# Sheet.net
KiCad netlist of a schematic drawn in Altium Designer
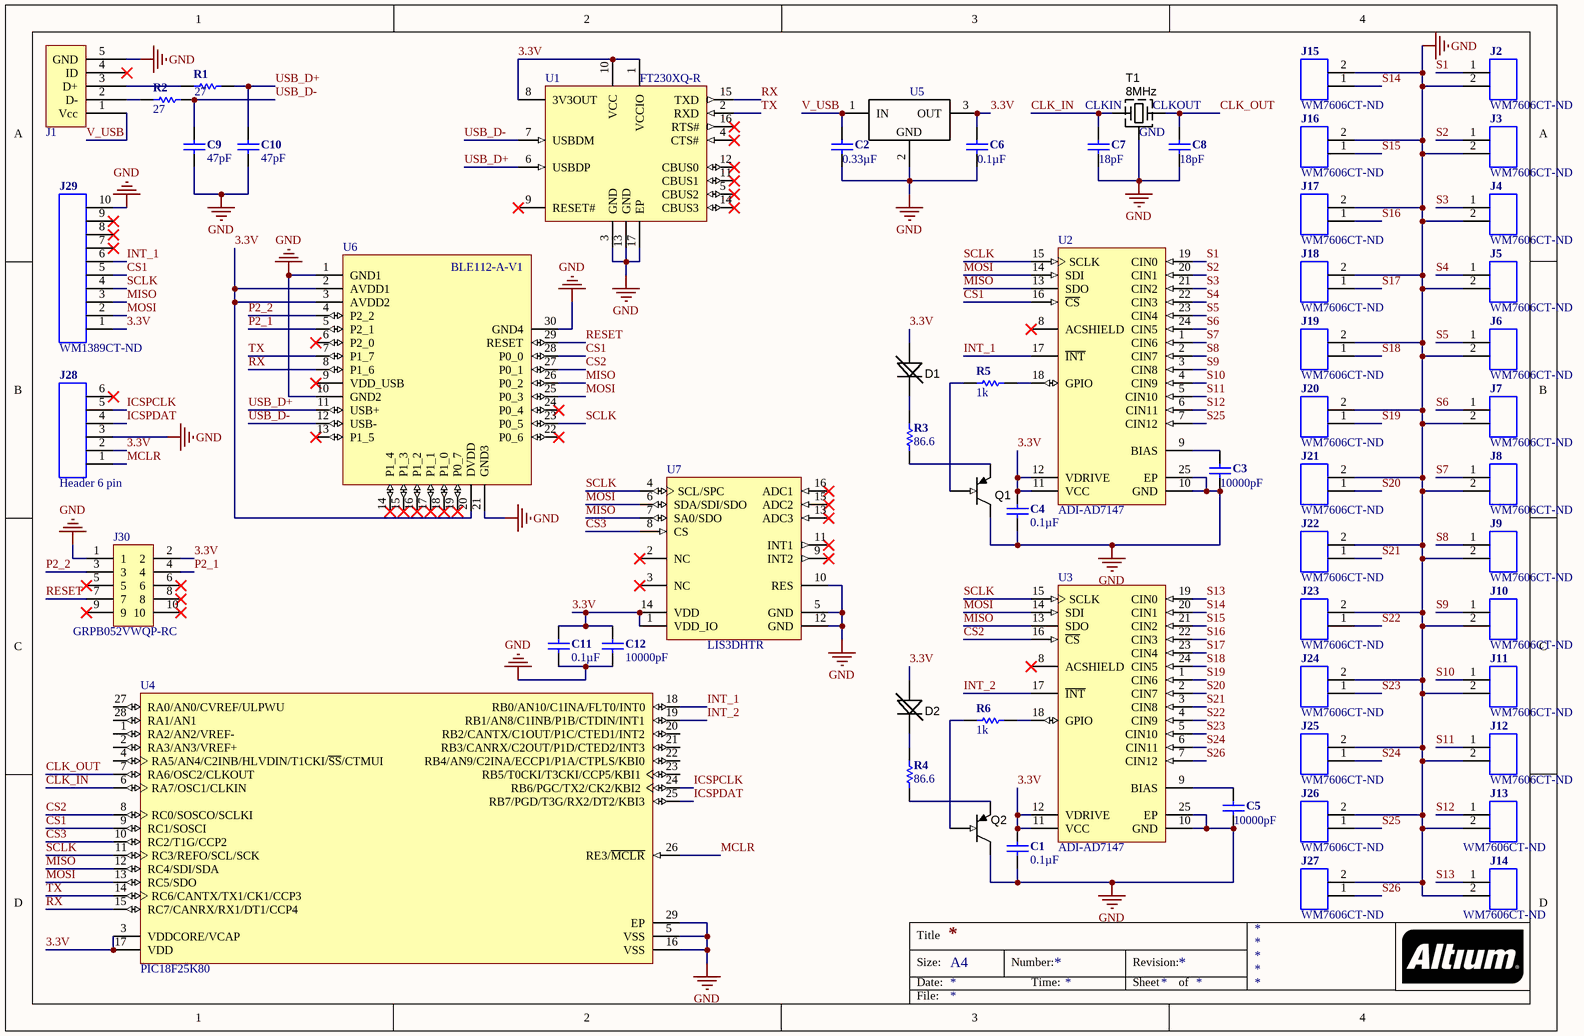
[diagram p0: Sheet.SchDoc]

(export (version "E")
  (design (tool "Eeschema 10.0.6"))
  (components
    (comp (ref "C1")
      (value "0.1µF")
      (footprint "CAP-0805(2012)-R")
      (description "___ OHM ___ mW 0805(2012) SMD")
      (fields
        (field (name "MANUFACTURER") "Yageo")
        (field (name "MANUFACTURER PART NUMBER") "CC0805KRX7R9BB104")
      )
      (libsource (lib "Glove") (part "C-0805(2012)"))
    )
    (comp (ref "C2")
      (value "0.33µF")
      (footprint "CAP-0805(2012)-R")
      (description "___ OHM ___ mW 0805(2012) SMD")
      (fields
        (field (name "MANUFACTURER") "Yageo")
        (field (name "MANUFACTURER PART NUMBER") "CC0805KKX7R7BB334")
      )
      (libsource (lib "Glove") (part "C-0805(2012)"))
    )
    (comp (ref "C3")
      (value "10000pF")
      (footprint "CAP-0805(2012)-R")
      (description "___ OHM ___ mW 0805(2012) SMD")
      (fields
        (field (name "MANUFACTURER") "Yageo")
        (field (name "MANUFACTURER PART NUMBER") "CC0805KRX7R9BB103")
      )
      (libsource (lib "Glove") (part "C-0805(2012)"))
    )
    (comp (ref "C4")
      (value "0.1µF")
      (footprint "CAP-0805(2012)-R")
      (description "___ OHM ___ mW 0805(2012) SMD")
      (fields
        (field (name "MANUFACTURER") "Yageo")
        (field (name "MANUFACTURER PART NUMBER") "CC0805KRX7R9BB104")
      )
      (libsource (lib "Glove") (part "C-0805(2012)"))
    )
    (comp (ref "C5")
      (value "10000pF")
      (footprint "CAP-0805(2012)-R")
      (description "___ OHM ___ mW 0805(2012) SMD")
      (fields
        (field (name "MANUFACTURER") "Yageo")
        (field (name "MANUFACTURER PART NUMBER") "CC0805KRX7R9BB103")
      )
      (libsource (lib "Glove") (part "C-0805(2012)"))
    )
    (comp (ref "C6")
      (value "0.1µF")
      (footprint "CAP-0805(2012)-R")
      (description "___ OHM ___ mW 0805(2012) SMD")
      (fields
        (field (name "MANUFACTURER") "Yageo")
        (field (name "MANUFACTURER PART NUMBER") "CC0805KRX7R9BB104")
      )
      (libsource (lib "Glove") (part "C-0805(2012)"))
    )
    (comp (ref "C7")
      (value "18pF")
      (footprint "CAP-0805(2012)-R")
      (description "___ OHM ___ mW 0805(2012) SMD")
      (fields
        (field (name "MANUFACTURER") "Yageo")
        (field (name "MANUFACTURER PART NUMBER") "CC0805JRNPO9BN180")
      )
      (libsource (lib "Glove") (part "C-0805(2012)"))
    )
    (comp (ref "C8")
      (value "18pF")
      (footprint "CAP-0805(2012)-R")
      (description "___ OHM ___ mW 0805(2012) SMD")
      (fields
        (field (name "MANUFACTURER") "Yageo")
        (field (name "MANUFACTURER PART NUMBER") "CC0805JRNPO9BN180")
      )
      (libsource (lib "Glove") (part "C-0805(2012)"))
    )
    (comp (ref "C9")
      (value "47pF")
      (footprint "CAP-0805(2012)-R")
      (description "___ OHM ___ mW 0805(2012) SMD")
      (fields
        (field (name "MANUFACTURER") "Yageo")
        (field (name "MANUFACTURER PART NUMBER") "CC0805JRNPO9BN470")
      )
      (libsource (lib "Glove") (part "C-0805(2012)"))
    )
    (comp (ref "C10")
      (value "47pF")
      (footprint "CAP-0805(2012)-R")
      (description "___ OHM ___ mW 0805(2012) SMD")
      (fields
        (field (name "MANUFACTURER") "Yageo")
        (field (name "MANUFACTURER PART NUMBER") "CC0805JRNPO9BN470")
      )
      (libsource (lib "Glove") (part "C-0805(2012)"))
    )
    (comp (ref "C11")
      (value "0.1µF")
      (footprint "CAP-0805(2012)-R")
      (description "___ OHM ___ mW 0805(2012) SMD")
      (fields
        (field (name "MANUFACTURER") "Yageo")
        (field (name "MANUFACTURER PART NUMBER") "CC0805KRX7R9BB104")
      )
      (libsource (lib "Glove") (part "C-0805(2012)"))
    )
    (comp (ref "C12")
      (value "10000pF")
      (footprint "CAP-0805(2012)-R")
      (description "___ OHM ___ mW 0805(2012) SMD")
      (fields
        (field (name "MANUFACTURER") "Yageo")
        (field (name "MANUFACTURER PART NUMBER") "CC0805KRX7R9BB103")
      )
      (libsource (lib "Glove") (part "C-0805(2012)"))
    )
    (comp (ref "D1")
      (value "YELLOW")
      (footprint "LED-0805-A")
      (description "LED, 0805 SMD, YELLOW")
      (fields
        (field (name "MANUFACTURER") "OSRAM Opto Semiconductors Inc.")
        (field (name "MANUFACTURER PART NUMBER") "LY R976-PS-36")
      )
      (libsource (lib "Glove") (part "LED_0805_YELLOW"))
    )
    (comp (ref "D2")
      (value "YELLOW")
      (footprint "LED-0805-A")
      (description "LED, 0805 SMD, YELLOW")
      (fields
        (field (name "MANUFACTURER") "OSRAM Opto Semiconductors Inc.")
        (field (name "MANUFACTURER PART NUMBER") "LY R976-PS-36")
      )
      (libsource (lib "Glove") (part "LED_0805_YELLOW"))
    )
    (comp (ref "J1")
      (value "USB")
      (footprint "USB_Connector_5P_MICRO_USB_FCI")
      (description "USB_Connector_5P_MICRO_USB_FCI")
      (fields (field (name "MANUFACTURER") "FCI") (field (name "MANUFACTURER PART NUMBER") "10118194-0001LF"))
      (libsource (lib "Glove") (part "USB"))
    )
    (comp (ref "J2")
      (value "Header 2 pin")
      (footprint "WM7606CT-ND")
      (description "Header, 2 pin, .1 pitch")
      (fields
        (field (name "MANUFACTURER") "Molex, LLC")
        (field (name "MANUFACTURER PART NUMBER") "0533980271")
        (field (name "SUPPLIER PART NUMBER 1") "WM7606CT-ND")
      )
      (libsource (lib "") (part "CON-2Pin_1"))
    )
    (comp (ref "J3")
      (value "Header 2 pin")
      (footprint "WM7606CT-ND")
      (description "Header, 2 pin, .1 pitch")
      (fields
        (field (name "MANUFACTURER") "Molex, LLC")
        (field (name "MANUFACTURER PART NUMBER") "0533980271")
        (field (name "SUPPLIER PART NUMBER 1") "WM7606CT-ND")
      )
      (libsource (lib "") (part "CON-2Pin_1"))
    )
    (comp (ref "J4")
      (value "Header 2 pin")
      (footprint "WM7606CT-ND")
      (description "Header, 2 pin, .1 pitch")
      (fields
        (field (name "MANUFACTURER") "Molex, LLC")
        (field (name "MANUFACTURER PART NUMBER") "0533980271")
        (field (name "SUPPLIER PART NUMBER 1") "WM7606CT-ND")
      )
      (libsource (lib "") (part "CON-2Pin_1"))
    )
    (comp (ref "J5")
      (value "Header 2 pin")
      (footprint "WM7606CT-ND")
      (description "Header, 2 pin, .1 pitch")
      (fields
        (field (name "MANUFACTURER") "Molex, LLC")
        (field (name "MANUFACTURER PART NUMBER") "0533980271")
        (field (name "SUPPLIER PART NUMBER 1") "WM7606CT-ND")
      )
      (libsource (lib "") (part "CON-2Pin_1"))
    )
    (comp (ref "J6")
      (value "Header 2 pin")
      (footprint "WM7606CT-ND")
      (description "Header, 2 pin, .1 pitch")
      (fields
        (field (name "MANUFACTURER") "Molex, LLC")
        (field (name "MANUFACTURER PART NUMBER") "0533980271")
        (field (name "SUPPLIER PART NUMBER 1") "WM7606CT-ND")
      )
      (libsource (lib "") (part "CON-2Pin_1"))
    )
    (comp (ref "J7")
      (value "Header 2 pin")
      (footprint "WM7606CT-ND")
      (description "Header, 2 pin, .1 pitch")
      (fields
        (field (name "MANUFACTURER") "Molex, LLC")
        (field (name "MANUFACTURER PART NUMBER") "0533980271")
        (field (name "SUPPLIER PART NUMBER 1") "WM7606CT-ND")
      )
      (libsource (lib "") (part "CON-2Pin_1"))
    )
    (comp (ref "J8")
      (value "Header 2 pin")
      (footprint "WM7606CT-ND")
      (description "Header, 2 pin, .1 pitch")
      (fields
        (field (name "MANUFACTURER") "Molex, LLC")
        (field (name "MANUFACTURER PART NUMBER") "0533980271")
        (field (name "SUPPLIER PART NUMBER 1") "WM7606CT-ND")
      )
      (libsource (lib "") (part "CON-2Pin_1"))
    )
    (comp (ref "J9")
      (value "Header 2 pin")
      (footprint "WM7606CT-ND")
      (description "Header, 2 pin, .1 pitch")
      (fields
        (field (name "MANUFACTURER") "Molex, LLC")
        (field (name "MANUFACTURER PART NUMBER") "0533980271")
        (field (name "SUPPLIER PART NUMBER 1") "WM7606CT-ND")
      )
      (libsource (lib "") (part "CON-2Pin_1"))
    )
    (comp (ref "J10")
      (value "Header 2 pin")
      (footprint "WM7606CT-ND")
      (description "Header, 2 pin, .1 pitch")
      (fields
        (field (name "MANUFACTURER") "Molex, LLC")
        (field (name "MANUFACTURER PART NUMBER") "0533980271")
        (field (name "SUPPLIER PART NUMBER 1") "WM7606CT-ND")
      )
      (libsource (lib "") (part "CON-2Pin_1"))
    )
    (comp (ref "J11")
      (value "Header 2 pin")
      (footprint "WM7606CT-ND")
      (description "Header, 2 pin, .1 pitch")
      (fields
        (field (name "MANUFACTURER") "Molex, LLC")
        (field (name "MANUFACTURER PART NUMBER") "0533980271")
        (field (name "SUPPLIER PART NUMBER 1") "WM7606CT-ND")
      )
      (libsource (lib "") (part "CON-2Pin_1"))
    )
    (comp (ref "J12")
      (value "Header 2 pin")
      (footprint "WM7606CT-ND")
      (description "Header, 2 pin, .1 pitch")
      (fields
        (field (name "MANUFACTURER") "Molex, LLC")
        (field (name "MANUFACTURER PART NUMBER") "0533980271")
        (field (name "SUPPLIER PART NUMBER 1") "WM7606CT-ND")
      )
      (libsource (lib "") (part "CON-2Pin_1"))
    )
    (comp (ref "J13")
      (value "Header 2 pin")
      (footprint "WM7606CT-ND")
      (description "Header, 2 pin, .1 pitch")
      (fields
        (field (name "MANUFACTURER") "Molex, LLC")
        (field (name "MANUFACTURER PART NUMBER") "0533980271")
        (field (name "SUPPLIER PART NUMBER 1") "WM7606CT-ND")
      )
      (libsource (lib "") (part "CON-2Pin_1"))
    )
    (comp (ref "J14")
      (value "Header 2 pin")
      (footprint "WM7606CT-ND")
      (description "Header, 2 pin, .1 pitch")
      (fields
        (field (name "MANUFACTURER") "Molex, LLC")
        (field (name "MANUFACTURER PART NUMBER") "0533980271")
        (field (name "SUPPLIER PART NUMBER 1") "WM7606CT-ND")
      )
      (libsource (lib "") (part "CON-2Pin_1"))
    )
    (comp (ref "J15")
      (value "Header 2 pin")
      (footprint "WM7606CT-ND")
      (description "Header, 2 pin, .1 pitch")
      (fields
        (field (name "MANUFACTURER") "Molex, LLC")
        (field (name "MANUFACTURER PART NUMBER") "0533980271")
        (field (name "SUPPLIER PART NUMBER 1") "WM7606CT-ND")
      )
      (libsource (lib "Glove") (part "CON-2Pin"))
    )
    (comp (ref "J16")
      (value "Header 2 pin")
      (footprint "WM7606CT-ND")
      (description "Header, 2 pin, .1 pitch")
      (fields
        (field (name "MANUFACTURER") "Molex, LLC")
        (field (name "MANUFACTURER PART NUMBER") "0533980271")
        (field (name "SUPPLIER PART NUMBER 1") "WM7606CT-ND")
      )
      (libsource (lib "Glove") (part "CON-2Pin"))
    )
    (comp (ref "J17")
      (value "Header 2 pin")
      (footprint "WM7606CT-ND")
      (description "Header, 2 pin, .1 pitch")
      (fields
        (field (name "MANUFACTURER") "Molex, LLC")
        (field (name "MANUFACTURER PART NUMBER") "0533980271")
        (field (name "SUPPLIER PART NUMBER 1") "WM7606CT-ND")
      )
      (libsource (lib "Glove") (part "CON-2Pin"))
    )
    (comp (ref "J18")
      (value "Header 2 pin")
      (footprint "WM7606CT-ND")
      (description "Header, 2 pin, .1 pitch")
      (fields
        (field (name "MANUFACTURER") "Molex, LLC")
        (field (name "MANUFACTURER PART NUMBER") "0533980271")
        (field (name "SUPPLIER PART NUMBER 1") "WM7606CT-ND")
      )
      (libsource (lib "Glove") (part "CON-2Pin"))
    )
    (comp (ref "J19")
      (value "Header 2 pin")
      (footprint "WM7606CT-ND")
      (description "Header, 2 pin, .1 pitch")
      (fields
        (field (name "MANUFACTURER") "Molex, LLC")
        (field (name "MANUFACTURER PART NUMBER") "0533980271")
        (field (name "SUPPLIER PART NUMBER 1") "WM7606CT-ND")
      )
      (libsource (lib "Glove") (part "CON-2Pin"))
    )
    (comp (ref "J20")
      (value "Header 2 pin")
      (footprint "WM7606CT-ND")
      (description "Header, 2 pin, .1 pitch")
      (fields
        (field (name "MANUFACTURER") "Molex, LLC")
        (field (name "MANUFACTURER PART NUMBER") "0533980271")
        (field (name "SUPPLIER PART NUMBER 1") "WM7606CT-ND")
      )
      (libsource (lib "Glove") (part "CON-2Pin"))
    )
    (comp (ref "J21")
      (value "Header 2 pin")
      (footprint "WM7606CT-ND")
      (description "Header, 2 pin, .1 pitch")
      (fields
        (field (name "MANUFACTURER") "Molex, LLC")
        (field (name "MANUFACTURER PART NUMBER") "0533980271")
        (field (name "SUPPLIER PART NUMBER 1") "WM7606CT-ND")
      )
      (libsource (lib "Glove") (part "CON-2Pin"))
    )
    (comp (ref "J22")
      (value "Header 2 pin")
      (footprint "WM7606CT-ND")
      (description "Header, 2 pin, .1 pitch")
      (fields
        (field (name "MANUFACTURER") "Molex, LLC")
        (field (name "MANUFACTURER PART NUMBER") "0533980271")
        (field (name "SUPPLIER PART NUMBER 1") "WM7606CT-ND")
      )
      (libsource (lib "Glove") (part "CON-2Pin"))
    )
    (comp (ref "J23")
      (value "Header 2 pin")
      (footprint "WM7606CT-ND")
      (description "Header, 2 pin, .1 pitch")
      (fields
        (field (name "MANUFACTURER") "Molex, LLC")
        (field (name "MANUFACTURER PART NUMBER") "0533980271")
        (field (name "SUPPLIER PART NUMBER 1") "WM7606CT-ND")
      )
      (libsource (lib "Glove") (part "CON-2Pin"))
    )
    (comp (ref "J24")
      (value "Header 2 pin")
      (footprint "WM7606CT-ND")
      (description "Header, 2 pin, .1 pitch")
      (fields
        (field (name "MANUFACTURER") "Molex, LLC")
        (field (name "MANUFACTURER PART NUMBER") "0533980271")
        (field (name "SUPPLIER PART NUMBER 1") "WM7606CT-ND")
      )
      (libsource (lib "Glove") (part "CON-2Pin"))
    )
    (comp (ref "J25")
      (value "Header 2 pin")
      (footprint "WM7606CT-ND")
      (description "Header, 2 pin, .1 pitch")
      (fields
        (field (name "MANUFACTURER") "Molex, LLC")
        (field (name "MANUFACTURER PART NUMBER") "0533980271")
        (field (name "SUPPLIER PART NUMBER 1") "WM7606CT-ND")
      )
      (libsource (lib "Glove") (part "CON-2Pin"))
    )
    (comp (ref "J26")
      (value "Header 2 pin")
      (footprint "WM7606CT-ND")
      (description "Header, 2 pin, .1 pitch")
      (fields
        (field (name "MANUFACTURER") "Molex, LLC")
        (field (name "MANUFACTURER PART NUMBER") "0533980271")
        (field (name "SUPPLIER PART NUMBER 1") "WM7606CT-ND")
      )
      (libsource (lib "Glove") (part "CON-2Pin"))
    )
    (comp (ref "J27")
      (value "Header 2 pin")
      (footprint "WM7606CT-ND")
      (description "Header, 2 pin, .1 pitch")
      (fields
        (field (name "MANUFACTURER") "Molex, LLC")
        (field (name "MANUFACTURER PART NUMBER") "0533980271")
        (field (name "SUPPLIER PART NUMBER 1") "WM7606CT-ND")
      )
      (libsource (lib "Glove") (part "CON-2Pin"))
    )
    (comp (ref "J28")
      (value "Header 6 pin")
      (footprint "HEADER-6-100mil")
      (description "Header, 6 pin, .1 pitch")
      (fields
        (field (name "MANUFACTURER") "TE Connectivity / AMP")
        (field (name "MANUFACTURER PART NUMBER") "4-103327-6")
      )
      (libsource (lib "Glove") (part "CON-6Pin-100Mil"))
    )
    (comp (ref "J29")
      (value "Header 10 pin")
      (footprint "MOLEX-503480-1000")
      (description "Header, 10 pin, .50mm pitch")
      (fields
        (field (name "MANUFACTURER") "Molex, LLC")
        (field (name "MANUFACTURER PART NUMBER") "5034801000")
        (field (name "SUPPLIER PART NUMBER 1") "WM1389CT-ND")
      )
      (libsource (lib "Glove") (part "WM1389CT-ND"))
    )
    (comp (ref "J30")
      (value "GRPB052VWQP-RC")
      (footprint "GRPB052VWQP-RC")
      (description "CONN HEADER .050\" 10PS DL SMD AU")
      (fields (field (name "MANUFACTURER") "Sullins Connector Solutions"))
      (libsource (lib "UCSD Protolab") (part "GRPB052VWQP-RC"))
    )
    (comp (ref "Q1")
      (value "~")
      (footprint "SOT23-3")
      (description "Transistor PNP")
      (fields
        (field (name "MANUFACTURER") "Diodes Incorporated")
        (field (name "MANUFACTURER PART NUMBER") "FMMT591TA")
      )
      (libsource (lib "Glove") (part "FMMT591CT-ND"))
    )
    (comp (ref "Q2")
      (value "~")
      (footprint "SOT23-3")
      (description "Transistor PNP")
      (fields
        (field (name "MANUFACTURER") "Diodes Incorporated")
        (field (name "MANUFACTURER PART NUMBER") "FMMT591TA")
      )
      (libsource (lib "Glove") (part "FMMT591CT-ND"))
    )
    (comp (ref "R1")
      (value "27")
      (footprint "R-0805(2012)-R")
      (description "___ OHM ___ mW 0805(2012) SMD")
      (fields
        (field (name "MANUFACTURER") "Yageo")
        (field (name "MANUFACTURER PART NUMBER") "RC0805FR-0727RL")
      )
      (libsource (lib "Glove") (part "R-0805(2012)"))
    )
    (comp (ref "R2")
      (value "27")
      (footprint "R-0805(2012)-R")
      (description "___ OHM ___ mW 0805(2012) SMD")
      (fields
        (field (name "MANUFACTURER") "Yageo")
        (field (name "MANUFACTURER PART NUMBER") "RC0805FR-0727RL")
      )
      (libsource (lib "Glove") (part "R-0805(2012)"))
    )
    (comp (ref "R3")
      (value "86.6")
      (footprint "R-0805(2012)-R")
      (description "___ OHM ___ mW 0805(2012) SMD")
      (fields
        (field (name "MANUFACTURER") "Yageo")
        (field (name "MANUFACTURER PART NUMBER") "RC0805FR-0786R6L")
      )
      (libsource (lib "CLB-Schematic-Library") (part "R-0805(2012)"))
    )
    (comp (ref "R4")
      (value "86.6")
      (footprint "R-0805(2012)-R")
      (description "___ OHM ___ mW 0805(2012) SMD")
      (fields
        (field (name "MANUFACTURER") "Yageo")
        (field (name "MANUFACTURER PART NUMBER") "RC0805FR-0786R6L")
      )
      (libsource (lib "CLB-Schematic-Library") (part "R-0805(2012)"))
    )
    (comp (ref "R5")
      (value "1k")
      (footprint "R-0805(2012)-R")
      (description "___ OHM ___ mW 0805(2012) SMD")
      (fields
        (field (name "MANUFACTURER") "Yageo")
        (field (name "MANUFACTURER PART NUMBER") "RC0805JR-071KL")
      )
      (libsource (lib "Glove") (part "R-0805(2012)"))
    )
    (comp (ref "R6")
      (value "1k")
      (footprint "R-0805(2012)-R")
      (description "___ OHM ___ mW 0805(2012) SMD")
      (fields
        (field (name "MANUFACTURER") "Yageo")
        (field (name "MANUFACTURER PART NUMBER") "RC0805JR-071KL")
      )
      (libsource (lib "Glove") (part "R-0805(2012)"))
    )
    (comp (ref "T1")
      (value "8MHz")
      (footprint "CRYSTAL-8MHZ")
      (description "Oscillator Crystal 8MHz 10ppm")
      (fields
        (field (name "MANUFACTURER") "ABRACON")
        (field (name "MANUFACTURER PART NUMBER") "ABMM2-8.000MHZ-E2-T")
      )
      (libsource (lib "Glove") (part "CRYSTAL_8MHz"))
    )
    (comp (ref "U1")
      (value "FT230XQ-R")
      (footprint "QFN-16")
      (fields (field (name "MANUFACTURER") "FTDI"))
      (libsource (lib "Glove") (part "FT230XQ-R"))
    )
    (comp (ref "U2")
      (value "ADI-AD7147")
      (footprint "LFCSP_WQ")
      (libsource (lib "Glove") (part "ADI-AD7147"))
    )
    (comp (ref "U3")
      (value "ADI-AD7147")
      (footprint "LFCSP_WQ")
      (libsource (lib "Glove") (part "ADI-AD7147"))
    )
    (comp (ref "U4")
      (value "PIC18F25K80")
      (footprint "MCHP-QFN-S-MM28_N")
      (libsource (lib "Glove") (part "PIC18F25K80"))
    )
    (comp (ref "U5")
      (value "L78L33ACUTR")
      (footprint "SOT89-3")
      (fields (field (name "MANUFACTURER") "STMicroelectronics"))
      (libsource (lib "Glove") (part "L78L33ACUTR"))
    )
    (comp (ref "U6")
      (value "BLE112-A-V1")
      (footprint "BLE112-A-V1")
      (description "CLASS 2 BLTOOTH 4.0 MODULE")
      (fields (field (name "MANUFACTURER") "Silicon Labs"))
      (libsource (lib "UCSD Protolab") (part "BLE112-A-V1"))
    )
    (comp (ref "U7")
      (value "LIS3DHTR")
      (footprint "STM-LGA-16_N")
      (fields (field (name "MANUFACTURER") "STMicroelectronics"))
      (libsource (lib "Altium Content Vault") (part "STM-LIS3DH-LGA-16"))
    )
  )
  (nets
    (net (code "1") (name "/3.3V") (class "Default")
      (node (ref "C1") (pin "1") (pinfunction "1_1") (pintype "passive"))
      (node (ref "C11") (pin "2") (pinfunction "2_2") (pintype "passive"))
      (node (ref "C12") (pin "2") (pinfunction "2_2") (pintype "passive"))
      (node (ref "C4") (pin "1") (pinfunction "1_1") (pintype "passive"))
      (node (ref "C6") (pin "1") (pinfunction "1_1") (pintype "passive"))
      (node (ref "D1") (pin "A") (pinfunction "A_A") (pintype "passive"))
      (node (ref "D2") (pin "A") (pinfunction "A_A") (pintype "passive"))
      (node (ref "J28") (pin "2") (pinfunction "2_2") (pintype "passive"))
      (node (ref "J29") (pin "1") (pinfunction "1_1") (pintype "passive"))
      (node (ref "J30") (pin "2") (pinfunction "2_2") (pintype "passive"))
      (node (ref "U1") (pin "1") (pinfunction "VCCIO_1") (pintype "power_in"))
      (node (ref "U1") (pin "10") (pinfunction "VCC_10") (pintype "power_in"))
      (node (ref "U1") (pin "8") (pinfunction "3V3OUT_8") (pintype "power_in"))
      (node (ref "U2") (pin "11") (pinfunction "VCC_11") (pintype "power_in"))
      (node (ref "U2") (pin "12") (pinfunction "VDRIVE_12") (pintype "power_in"))
      (node (ref "U3") (pin "11") (pinfunction "VCC_11") (pintype "power_in"))
      (node (ref "U3") (pin "12") (pinfunction "VDRIVE_12") (pintype "power_in"))
      (node (ref "U4") (pin "17") (pinfunction "VDD_17") (pintype "power_in"))
      (node (ref "U4") (pin "3") (pinfunction "VDDCORE/VCAP_3") (pintype "power_in"))
      (node (ref "U5") (pin "3") (pinfunction "OUT_3") (pintype "power_in"))
      (node (ref "U6") (pin "2") (pinfunction "AVDD1_2") (pintype "power_in"))
      (node (ref "U6") (pin "20") (pinfunction "DVDD_20") (pintype "power_in"))
      (node (ref "U6") (pin "3") (pinfunction "AVDD2_3") (pintype "power_in"))
      (node (ref "U7") (pin "1") (pinfunction "VDD_IO_1") (pintype "power_in"))
      (node (ref "U7") (pin "14") (pinfunction "VDD_14") (pintype "power_in"))
    )
    (net (code "2") (name "/CLK_IN") (class "Default")
      (node (ref "C7") (pin "1") (pinfunction "1_1") (pintype "passive"))
      (node (ref "T1") (pin "1") (pinfunction "CLKIN_1") (pintype "passive"))
      (node (ref "U4") (pin "6") (pinfunction "RA7/OSC1/CLKIN_6") (pintype "bidirectional"))
    )
    (net (code "3") (name "/CLK_OUT") (class "Default")
      (node (ref "C8") (pin "1") (pinfunction "1_1") (pintype "passive"))
      (node (ref "T1") (pin "3") (pinfunction "X_3") (pintype "passive"))
      (node (ref "U4") (pin "7") (pinfunction "RA6/OSC2/CLKOUT_7") (pintype "bidirectional"))
    )
    (net (code "4") (name "/CS1") (class "Default")
      (node (ref "J29") (pin "5") (pinfunction "5_5") (pintype "passive"))
      (node (ref "U2") (pin "16") (pinfunction "~{CS}_16") (pintype "input"))
      (node (ref "U4") (pin "9") (pinfunction "RC1/SOSCI_9") (pintype "bidirectional"))
      (node (ref "U6") (pin "28") (pinfunction "P0_0_28") (pintype "bidirectional"))
    )
    (net (code "5") (name "/CS2") (class "Default")
      (node (ref "U3") (pin "16") (pinfunction "~{CS}_16") (pintype "input"))
      (node (ref "U4") (pin "8") (pinfunction "RC0/SOSCO/SCLKI_8") (pintype "bidirectional"))
      (node (ref "U6") (pin "27") (pinfunction "P0_1_27") (pintype "bidirectional"))
    )
    (net (code "6") (name "/CS3") (class "Default")
      (node (ref "U4") (pin "10") (pinfunction "RC2/T1G/CCP2_10") (pintype "bidirectional"))
      (node (ref "U7") (pin "8") (pinfunction "CS_8") (pintype "input"))
    )
    (net (code "7") (name "/ICSPCLK") (class "Default")
      (node (ref "J28") (pin "5") (pinfunction "5_5") (pintype "passive"))
      (node (ref "U4") (pin "24") (pinfunction "RB6/PGC/TX2/CK2/KBI2_24") (pintype "bidirectional"))
    )
    (net (code "8") (name "/ICSPDAT") (class "Default")
      (node (ref "J28") (pin "4") (pinfunction "4_4") (pintype "passive"))
      (node (ref "U4") (pin "25") (pinfunction "RB7/PGD/T3G/RX2/DT2/KBI3_25") (pintype "bidirectional"))
    )
    (net (code "9") (name "/INT_1") (class "Default")
      (node (ref "J29") (pin "6") (pinfunction "6_6") (pintype "passive"))
      (node (ref "U2") (pin "17") (pinfunction "~{INT}_17") (pintype "open_collector"))
      (node (ref "U4") (pin "18") (pinfunction "RB0/AN10/C1INA/FLT0/INT0_18") (pintype "bidirectional"))
    )
    (net (code "10") (name "/INT_2") (class "Default")
      (node (ref "U3") (pin "17") (pinfunction "~{INT}_17") (pintype "open_collector"))
      (node (ref "U4") (pin "19") (pinfunction "RB1/AN8/C1INB/P1B/CTDIN/INT1_19") (pintype "bidirectional"))
    )
    (net (code "11") (name "/MCLR") (class "Default")
      (node (ref "J28") (pin "1") (pinfunction "1_1") (pintype "passive"))
      (node (ref "U4") (pin "26") (pinfunction "RE3/~{MCLR}_26") (pintype "input"))
    )
    (net (code "12") (name "/MISO") (class "Default")
      (node (ref "J29") (pin "3") (pinfunction "3_3") (pintype "passive"))
      (node (ref "U2") (pin "13") (pinfunction "SDO_13") (pintype "tri_state"))
      (node (ref "U3") (pin "13") (pinfunction "SDO_13") (pintype "tri_state"))
      (node (ref "U4") (pin "12") (pinfunction "RC4/SDI/SDA_12") (pintype "bidirectional"))
      (node (ref "U6") (pin "26") (pinfunction "P0_2_26") (pintype "bidirectional"))
      (node (ref "U7") (pin "7") (pinfunction "SA0/SDO_7") (pintype "bidirectional"))
    )
    (net (code "13") (name "/MOSI") (class "Default")
      (node (ref "J29") (pin "2") (pinfunction "2_2") (pintype "passive"))
      (node (ref "U2") (pin "14") (pinfunction "SDI_14") (pintype "input"))
      (node (ref "U3") (pin "14") (pinfunction "SDI_14") (pintype "input"))
      (node (ref "U4") (pin "13") (pinfunction "RC5/SDO_13") (pintype "bidirectional"))
      (node (ref "U6") (pin "25") (pinfunction "P0_3_25") (pintype "bidirectional"))
      (node (ref "U7") (pin "6") (pinfunction "SDA/SDI/SDO_6") (pintype "bidirectional"))
    )
    (net (code "14") (name "/P2_1") (class "Default")
      (node (ref "J30") (pin "4") (pinfunction "4_4") (pintype "passive"))
      (node (ref "U6") (pin "5") (pinfunction "P2_1_5") (pintype "bidirectional"))
    )
    (net (code "15") (name "/P2_2") (class "Default")
      (node (ref "J30") (pin "3") (pinfunction "3_3") (pintype "passive"))
      (node (ref "U6") (pin "4") (pinfunction "P2_2_4") (pintype "bidirectional"))
    )
    (net (code "16") (name "/RESET") (class "Default")
      (node (ref "J30") (pin "7") (pinfunction "7_7") (pintype "passive"))
      (node (ref "U6") (pin "29") (pinfunction "RESET_29") (pintype "bidirectional"))
    )
    (net (code "17") (name "/RX") (class "Default")
      (node (ref "U1") (pin "15") (pinfunction "TXD_15") (pintype "output"))
      (node (ref "U4") (pin "15") (pinfunction "RC7/CANRX/RX1/DT1/CCP4_15") (pintype "bidirectional"))
      (node (ref "U6") (pin "8") (pinfunction "P1_6_8") (pintype "bidirectional"))
    )
    (net (code "18") (name "/S1") (class "Default")
      (node (ref "J2") (pin "1") (pinfunction "1_1") (pintype "passive"))
      (node (ref "U2") (pin "19") (pinfunction "CIN0_19") (pintype "input"))
    )
    (net (code "19") (name "/S2") (class "Default")
      (node (ref "J3") (pin "1") (pinfunction "1_1") (pintype "passive"))
      (node (ref "U2") (pin "20") (pinfunction "CIN1_20") (pintype "input"))
    )
    (net (code "20") (name "/S3") (class "Default")
      (node (ref "J4") (pin "1") (pinfunction "1_1") (pintype "passive"))
      (node (ref "U2") (pin "21") (pinfunction "CIN2_21") (pintype "input"))
    )
    (net (code "21") (name "/S4") (class "Default")
      (node (ref "J5") (pin "1") (pinfunction "1_1") (pintype "passive"))
      (node (ref "U2") (pin "22") (pinfunction "CIN3_22") (pintype "input"))
    )
    (net (code "22") (name "/S5") (class "Default")
      (node (ref "J6") (pin "1") (pinfunction "1_1") (pintype "passive"))
      (node (ref "U2") (pin "23") (pinfunction "CIN4_23") (pintype "input"))
    )
    (net (code "23") (name "/S6") (class "Default")
      (node (ref "J7") (pin "1") (pinfunction "1_1") (pintype "passive"))
      (node (ref "U2") (pin "24") (pinfunction "CIN5_24") (pintype "input"))
    )
    (net (code "24") (name "/S7") (class "Default")
      (node (ref "J8") (pin "1") (pinfunction "1_1") (pintype "passive"))
      (node (ref "U2") (pin "1") (pinfunction "CIN6_1") (pintype "input"))
    )
    (net (code "25") (name "/S8") (class "Default")
      (node (ref "J9") (pin "1") (pinfunction "1_1") (pintype "passive"))
      (node (ref "U2") (pin "2") (pinfunction "CIN7_2") (pintype "input"))
    )
    (net (code "26") (name "/S9") (class "Default")
      (node (ref "J10") (pin "1") (pinfunction "1_1") (pintype "passive"))
      (node (ref "U2") (pin "3") (pinfunction "CIN8_3") (pintype "input"))
    )
    (net (code "27") (name "/S10") (class "Default")
      (node (ref "J11") (pin "1") (pinfunction "1_1") (pintype "passive"))
      (node (ref "U2") (pin "4") (pinfunction "CIN9_4") (pintype "input"))
    )
    (net (code "28") (name "/S11") (class "Default")
      (node (ref "J12") (pin "1") (pinfunction "1_1") (pintype "passive"))
      (node (ref "U2") (pin "5") (pinfunction "CIN10_5") (pintype "input"))
    )
    (net (code "29") (name "/S12") (class "Default")
      (node (ref "J13") (pin "1") (pinfunction "1_1") (pintype "passive"))
      (node (ref "U2") (pin "6") (pinfunction "CIN11_6") (pintype "input"))
    )
    (net (code "30") (name "/S13") (class "Default")
      (node (ref "J14") (pin "1") (pinfunction "1_1") (pintype "passive"))
      (node (ref "U3") (pin "19") (pinfunction "CIN0_19") (pintype "input"))
    )
    (net (code "31") (name "/S14") (class "Default")
      (node (ref "J15") (pin "1") (pinfunction "1_1") (pintype "passive"))
      (node (ref "U3") (pin "20") (pinfunction "CIN1_20") (pintype "input"))
    )
    (net (code "32") (name "/S15") (class "Default")
      (node (ref "J16") (pin "1") (pinfunction "1_1") (pintype "passive"))
      (node (ref "U3") (pin "21") (pinfunction "CIN2_21") (pintype "input"))
    )
    (net (code "33") (name "/S16") (class "Default")
      (node (ref "J17") (pin "1") (pinfunction "1_1") (pintype "passive"))
      (node (ref "U3") (pin "22") (pinfunction "CIN3_22") (pintype "input"))
    )
    (net (code "34") (name "/S17") (class "Default")
      (node (ref "J18") (pin "1") (pinfunction "1_1") (pintype "passive"))
      (node (ref "U3") (pin "23") (pinfunction "CIN4_23") (pintype "input"))
    )
    (net (code "35") (name "/S18") (class "Default")
      (node (ref "J19") (pin "1") (pinfunction "1_1") (pintype "passive"))
      (node (ref "U3") (pin "24") (pinfunction "CIN5_24") (pintype "input"))
    )
    (net (code "36") (name "/S19") (class "Default")
      (node (ref "J20") (pin "1") (pinfunction "1_1") (pintype "passive"))
      (node (ref "U3") (pin "1") (pinfunction "CIN6_1") (pintype "input"))
    )
    (net (code "37") (name "/S20") (class "Default")
      (node (ref "J21") (pin "1") (pinfunction "1_1") (pintype "passive"))
      (node (ref "U3") (pin "2") (pinfunction "CIN7_2") (pintype "input"))
    )
    (net (code "38") (name "/S21") (class "Default")
      (node (ref "J22") (pin "1") (pinfunction "1_1") (pintype "passive"))
      (node (ref "U3") (pin "3") (pinfunction "CIN8_3") (pintype "input"))
    )
    (net (code "39") (name "/S22") (class "Default")
      (node (ref "J23") (pin "1") (pinfunction "1_1") (pintype "passive"))
      (node (ref "U3") (pin "4") (pinfunction "CIN9_4") (pintype "input"))
    )
    (net (code "40") (name "/S23") (class "Default")
      (node (ref "J24") (pin "1") (pinfunction "1_1") (pintype "passive"))
      (node (ref "U3") (pin "5") (pinfunction "CIN10_5") (pintype "input"))
    )
    (net (code "41") (name "/S24") (class "Default")
      (node (ref "J25") (pin "1") (pinfunction "1_1") (pintype "passive"))
      (node (ref "U3") (pin "6") (pinfunction "CIN11_6") (pintype "input"))
    )
    (net (code "42") (name "/S25") (class "Default")
      (node (ref "J26") (pin "1") (pinfunction "1_1") (pintype "passive"))
      (node (ref "U2") (pin "7") (pinfunction "CIN12_7") (pintype "input"))
    )
    (net (code "43") (name "/S26") (class "Default")
      (node (ref "J27") (pin "1") (pinfunction "1_1") (pintype "passive"))
      (node (ref "U3") (pin "7") (pinfunction "CIN12_7") (pintype "input"))
    )
    (net (code "44") (name "/SCLK") (class "Default")
      (node (ref "J29") (pin "4") (pinfunction "4_4") (pintype "passive"))
      (node (ref "U2") (pin "15") (pinfunction "SCLK_15") (pintype "input"))
      (node (ref "U3") (pin "15") (pinfunction "SCLK_15") (pintype "input"))
      (node (ref "U4") (pin "11") (pinfunction "RC3/REFO/SCL/SCK_11") (pintype "bidirectional"))
      (node (ref "U6") (pin "23") (pinfunction "P0_5_23") (pintype "bidirectional"))
      (node (ref "U7") (pin "4") (pinfunction "SCL/SPC_4") (pintype "bidirectional"))
    )
    (net (code "45") (name "/TX") (class "Default")
      (node (ref "U1") (pin "2") (pinfunction "RXD_2") (pintype "input"))
      (node (ref "U4") (pin "14") (pinfunction "RC6/CANTX/TX1/CK1/CCP3_14") (pintype "bidirectional"))
      (node (ref "U6") (pin "7") (pinfunction "P1_7_7") (pintype "bidirectional"))
    )
    (net (code "46") (name "/USB_D+") (class "Default")
      (node (ref "C10") (pin "2") (pinfunction "2_2") (pintype "passive"))
      (node (ref "R1") (pin "2") (pinfunction "2_2") (pintype "passive"))
      (node (ref "U1") (pin "6") (pinfunction "USBDP_6") (pintype "input"))
      (node (ref "U6") (pin "11") (pinfunction "USB+_11") (pintype "bidirectional"))
    )
    (net (code "47") (name "/USB_D-") (class "Default")
      (node (ref "C9") (pin "2") (pinfunction "2_2") (pintype "passive"))
      (node (ref "R2") (pin "2") (pinfunction "2_2") (pintype "passive"))
      (node (ref "U1") (pin "7") (pinfunction "USBDM_7") (pintype "input"))
      (node (ref "U6") (pin "12") (pinfunction "USB-_12") (pintype "bidirectional"))
    )
    (net (code "48") (name "/V_USB") (class "Default")
      (node (ref "C2") (pin "1") (pinfunction "1_1") (pintype "passive"))
      (node (ref "J1") (pin "1") (pinfunction "Vcc_1") (pintype "passive"))
      (node (ref "U5") (pin "1") (pinfunction "IN_1") (pintype "passive"))
    )
    (net (code "49") (name "GND") (class "Default")
      (node (ref "C1") (pin "2") (pinfunction "2_2") (pintype "passive"))
      (node (ref "C10") (pin "1") (pinfunction "1_1") (pintype "passive"))
      (node (ref "C11") (pin "1") (pinfunction "1_1") (pintype "passive"))
      (node (ref "C12") (pin "1") (pinfunction "1_1") (pintype "passive"))
      (node (ref "C2") (pin "2") (pinfunction "2_2") (pintype "passive"))
      (node (ref "C3") (pin "2") (pinfunction "2_2") (pintype "passive"))
      (node (ref "C4") (pin "2") (pinfunction "2_2") (pintype "passive"))
      (node (ref "C5") (pin "2") (pinfunction "2_2") (pintype "passive"))
      (node (ref "C6") (pin "2") (pinfunction "2_2") (pintype "passive"))
      (node (ref "C7") (pin "2") (pinfunction "2_2") (pintype "passive"))
      (node (ref "C8") (pin "2") (pinfunction "2_2") (pintype "passive"))
      (node (ref "C9") (pin "1") (pinfunction "1_1") (pintype "passive"))
      (node (ref "J1") (pin "5") (pinfunction "GND_5") (pintype "passive"))
      (node (ref "J10") (pin "2") (pinfunction "2_2") (pintype "passive"))
      (node (ref "J11") (pin "2") (pinfunction "2_2") (pintype "passive"))
      (node (ref "J12") (pin "2") (pinfunction "2_2") (pintype "passive"))
      (node (ref "J13") (pin "2") (pinfunction "2_2") (pintype "passive"))
      (node (ref "J14") (pin "2") (pinfunction "2_2") (pintype "passive"))
      (node (ref "J15") (pin "2") (pinfunction "2_2") (pintype "passive"))
      (node (ref "J16") (pin "2") (pinfunction "2_2") (pintype "passive"))
      (node (ref "J17") (pin "2") (pinfunction "2_2") (pintype "passive"))
      (node (ref "J18") (pin "2") (pinfunction "2_2") (pintype "passive"))
      (node (ref "J19") (pin "2") (pinfunction "2_2") (pintype "passive"))
      (node (ref "J2") (pin "2") (pinfunction "2_2") (pintype "passive"))
      (node (ref "J20") (pin "2") (pinfunction "2_2") (pintype "passive"))
      (node (ref "J21") (pin "2") (pinfunction "2_2") (pintype "passive"))
      (node (ref "J22") (pin "2") (pinfunction "2_2") (pintype "passive"))
      (node (ref "J23") (pin "2") (pinfunction "2_2") (pintype "passive"))
      (node (ref "J24") (pin "2") (pinfunction "2_2") (pintype "passive"))
      (node (ref "J25") (pin "2") (pinfunction "2_2") (pintype "passive"))
      (node (ref "J26") (pin "2") (pinfunction "2_2") (pintype "passive"))
      (node (ref "J27") (pin "2") (pinfunction "2_2") (pintype "passive"))
      (node (ref "J28") (pin "3") (pinfunction "3_3") (pintype "passive"))
      (node (ref "J29") (pin "10") (pinfunction "10_10") (pintype "passive"))
      (node (ref "J3") (pin "2") (pinfunction "2_2") (pintype "passive"))
      (node (ref "J30") (pin "1") (pinfunction "1_1") (pintype "passive"))
      (node (ref "J4") (pin "2") (pinfunction "2_2") (pintype "passive"))
      (node (ref "J5") (pin "2") (pinfunction "2_2") (pintype "passive"))
      (node (ref "J6") (pin "2") (pinfunction "2_2") (pintype "passive"))
      (node (ref "J7") (pin "2") (pinfunction "2_2") (pintype "passive"))
      (node (ref "J8") (pin "2") (pinfunction "2_2") (pintype "passive"))
      (node (ref "J9") (pin "2") (pinfunction "2_2") (pintype "passive"))
      (node (ref "Q1") (pin "2") (pinfunction "C_2") (pintype "passive"))
      (node (ref "Q2") (pin "2") (pinfunction "C_2") (pintype "passive"))
      (node (ref "T1") (pin "2") (pinfunction "GND_2") (pintype "passive"))
      (node (ref "U1") (pin "13") (pinfunction "GND_13") (pintype "power_in"))
      (node (ref "U1") (pin "17") (pinfunction "EP_17") (pintype "power_in"))
      (node (ref "U1") (pin "3") (pinfunction "GND_3") (pintype "power_in"))
      (node (ref "U2") (pin "10") (pinfunction "GND_10") (pintype "power_in"))
      (node (ref "U2") (pin "25") (pinfunction "EP_25") (pintype "power_in"))
      (node (ref "U3") (pin "10") (pinfunction "GND_10") (pintype "power_in"))
      (node (ref "U3") (pin "25") (pinfunction "EP_25") (pintype "power_in"))
      (node (ref "U4") (pin "16") (pinfunction "VSS_16") (pintype "power_in"))
      (node (ref "U4") (pin "29") (pinfunction "EP_29") (pintype "power_in"))
      (node (ref "U4") (pin "5") (pinfunction "VSS_5") (pintype "power_in"))
      (node (ref "U5") (pin "2") (pinfunction "GND_2") (pintype "power_in"))
      (node (ref "U6") (pin "1") (pinfunction "GND1_1") (pintype "power_in"))
      (node (ref "U6") (pin "10") (pinfunction "GND2_10") (pintype "power_in"))
      (node (ref "U6") (pin "21") (pinfunction "GND3_21") (pintype "power_in"))
      (node (ref "U6") (pin "30") (pinfunction "GND4_30") (pintype "power_in"))
      (node (ref "U7") (pin "10") (pinfunction "RES_10") (pintype "power_in"))
      (node (ref "U7") (pin "12") (pinfunction "GND_12") (pintype "power_in"))
      (node (ref "U7") (pin "5") (pinfunction "GND_5") (pintype "power_in"))
    )
    (net (code "50") (name "Net-(D1-PadK)") (class "Default")
      (node (ref "D1") (pin "K") (pinfunction "K_K") (pintype "passive"))
      (node (ref "R3") (pin "2") (pinfunction "2_2") (pintype "passive"))
    )
    (net (code "51") (name "Net-(D2-PadK)") (class "Default")
      (node (ref "D2") (pin "K") (pinfunction "K_K") (pintype "passive"))
      (node (ref "R4") (pin "2") (pinfunction "2_2") (pintype "passive"))
    )
    (net (code "52") (name "Net-(J1-D+)") (class "Default")
      (node (ref "J1") (pin "3") (pinfunction "D+_3") (pintype "passive"))
      (node (ref "R1") (pin "1") (pinfunction "1_1") (pintype "passive"))
    )
    (net (code "53") (name "Net-(J1-D-)") (class "Default")
      (node (ref "J1") (pin "2") (pinfunction "D-_2") (pintype "passive"))
      (node (ref "R2") (pin "1") (pinfunction "1_1") (pintype "passive"))
    )
    (net (code "54") (name "Net-(Q1-B)") (class "Default")
      (node (ref "Q1") (pin "1") (pinfunction "B_1") (pintype "input"))
      (node (ref "R5") (pin "1") (pinfunction "1_1") (pintype "passive"))
    )
    (net (code "55") (name "Net-(Q1-E)") (class "Default")
      (node (ref "Q1") (pin "3") (pinfunction "E_3") (pintype "passive"))
      (node (ref "R3") (pin "1") (pinfunction "1_1") (pintype "passive"))
    )
    (net (code "56") (name "Net-(Q2-B)") (class "Default")
      (node (ref "Q2") (pin "1") (pinfunction "B_1") (pintype "input"))
      (node (ref "R6") (pin "2") (pinfunction "2_2") (pintype "passive"))
    )
    (net (code "57") (name "Net-(Q2-E)") (class "Default")
      (node (ref "Q2") (pin "3") (pinfunction "E_3") (pintype "passive"))
      (node (ref "R4") (pin "1") (pinfunction "1_1") (pintype "passive"))
    )
    (net (code "58") (name "Net-(U2-BIAS)") (class "Default")
      (node (ref "C3") (pin "1") (pinfunction "1_1") (pintype "passive"))
      (node (ref "U2") (pin "9") (pinfunction "BIAS_9") (pintype "passive"))
    )
    (net (code "59") (name "Net-(U2-GPIO)") (class "Default")
      (node (ref "R5") (pin "2") (pinfunction "2_2") (pintype "passive"))
      (node (ref "U2") (pin "18") (pinfunction "GPIO_18") (pintype "bidirectional"))
    )
    (net (code "60") (name "Net-(U3-BIAS)") (class "Default")
      (node (ref "C5") (pin "1") (pinfunction "1_1") (pintype "passive"))
      (node (ref "U3") (pin "9") (pinfunction "BIAS_9") (pintype "passive"))
    )
    (net (code "61") (name "Net-(U3-GPIO)") (class "Default")
      (node (ref "R6") (pin "1") (pinfunction "1_1") (pintype "passive"))
      (node (ref "U3") (pin "18") (pinfunction "GPIO_18") (pintype "bidirectional"))
    )
    (net (code "62") (name "unconnected-(J1-ID-Pad4)") (class "Default")
      (node (ref "J1") (pin "4") (pinfunction "ID_4") (pintype "passive+no_connect"))
    )
    (net (code "63") (name "unconnected-(J28-Pad6)") (class "Default")
      (node (ref "J28") (pin "6") (pinfunction "6_6") (pintype "passive+no_connect"))
    )
    (net (code "64") (name "unconnected-(J29-Pad7)") (class "Default")
      (node (ref "J29") (pin "7") (pinfunction "7_7") (pintype "passive+no_connect"))
    )
    (net (code "65") (name "unconnected-(J29-Pad8)") (class "Default")
      (node (ref "J29") (pin "8") (pinfunction "8_8") (pintype "passive+no_connect"))
    )
    (net (code "66") (name "unconnected-(J29-Pad9)") (class "Default")
      (node (ref "J29") (pin "9") (pinfunction "9_9") (pintype "passive+no_connect"))
    )
    (net (code "67") (name "unconnected-(J30-Pad5)") (class "Default")
      (node (ref "J30") (pin "5") (pinfunction "5_5") (pintype "passive+no_connect"))
    )
    (net (code "68") (name "unconnected-(J30-Pad6)") (class "Default")
      (node (ref "J30") (pin "6") (pinfunction "6_6") (pintype "passive+no_connect"))
    )
    (net (code "69") (name "unconnected-(J30-Pad8)") (class "Default")
      (node (ref "J30") (pin "8") (pinfunction "8_8") (pintype "passive+no_connect"))
    )
    (net (code "70") (name "unconnected-(J30-Pad9)") (class "Default")
      (node (ref "J30") (pin "9") (pinfunction "9_9") (pintype "passive+no_connect"))
    )
    (net (code "71") (name "unconnected-(J30-Pad10)") (class "Default")
      (node (ref "J30") (pin "10") (pinfunction "10_10") (pintype "passive+no_connect"))
    )
    (net (code "72") (name "unconnected-(U1-CBUS0-Pad12)") (class "Default")
      (node (ref "U1") (pin "12") (pinfunction "CBUS0_12") (pintype "bidirectional+no_connect"))
    )
    (net (code "73") (name "unconnected-(U1-CBUS1-Pad11)") (class "Default")
      (node (ref "U1") (pin "11") (pinfunction "CBUS1_11") (pintype "bidirectional+no_connect"))
    )
    (net (code "74") (name "unconnected-(U1-CBUS2-Pad5)") (class "Default")
      (node (ref "U1") (pin "5") (pinfunction "CBUS2_5") (pintype "bidirectional+no_connect"))
    )
    (net (code "75") (name "unconnected-(U1-CBUS3-Pad14)") (class "Default")
      (node (ref "U1") (pin "14") (pinfunction "CBUS3_14") (pintype "bidirectional+no_connect"))
    )
    (net (code "76") (name "unconnected-(U1-CTS#-Pad4)") (class "Default")
      (node (ref "U1") (pin "4") (pinfunction "CTS#_4") (pintype "input+no_connect"))
    )
    (net (code "77") (name "unconnected-(U1-RESET#-Pad9)") (class "Default")
      (node (ref "U1") (pin "9") (pinfunction "RESET#_9") (pintype "passive+no_connect"))
    )
    (net (code "78") (name "unconnected-(U1-RTS#-Pad16)") (class "Default")
      (node (ref "U1") (pin "16") (pinfunction "RTS#_16") (pintype "output+no_connect"))
    )
    (net (code "79") (name "unconnected-(U2-ACSHIELD-Pad8)") (class "Default")
      (node (ref "U2") (pin "8") (pinfunction "ACSHIELD_8") (pintype "passive+no_connect"))
    )
    (net (code "80") (name "unconnected-(U3-ACSHIELD-Pad8)") (class "Default")
      (node (ref "U3") (pin "8") (pinfunction "ACSHIELD_8") (pintype "passive+no_connect"))
    )
    (net (code "81") (name "unconnected-(U4-RA0{slash}AN0{slash}CVREF{slash}ULPWU-Pad27)") (class "Default")
      (node (ref "U4") (pin "27") (pinfunction "RA0/AN0/CVREF/ULPWU_27") (pintype "bidirectional"))
    )
    (net (code "82") (name "unconnected-(U4-RA1{slash}AN1-Pad28)") (class "Default")
      (node (ref "U4") (pin "28") (pinfunction "RA1/AN1_28") (pintype "bidirectional"))
    )
    (net (code "83") (name "unconnected-(U4-RA2{slash}AN2{slash}VREF--Pad1)") (class "Default")
      (node (ref "U4") (pin "1") (pinfunction "RA2/AN2/VREF-_1") (pintype "bidirectional"))
    )
    (net (code "84") (name "unconnected-(U4-RA3{slash}AN3{slash}VREF+-Pad2)") (class "Default")
      (node (ref "U4") (pin "2") (pinfunction "RA3/AN3/VREF+_2") (pintype "bidirectional"))
    )
    (net (code "85") (name "unconnected-(U4-RA5{slash}AN4{slash}C2INB{slash}HLVDIN{slash}T1CKI{slash}~{SS}{slash}CTMUI-Pad4)") (class "Default")
      (node (ref "U4") (pin "4") (pinfunction "RA5/AN4/C2INB/HLVDIN/T1CKI/~{SS}/CTMUI_4") (pintype "bidirectional"))
    )
    (net (code "86") (name "unconnected-(U4-RB2{slash}CANTX{slash}C1OUT{slash}P1C{slash}CTED1{slash}INT2-Pad20)") (class "Default")
      (node (ref "U4") (pin "20") (pinfunction "RB2/CANTX/C1OUT/P1C/CTED1/INT2_20") (pintype "bidirectional"))
    )
    (net (code "87") (name "unconnected-(U4-RB3{slash}CANRX{slash}C2OUT{slash}P1D{slash}CTED2{slash}INT3-Pad21)") (class "Default")
      (node (ref "U4") (pin "21") (pinfunction "RB3/CANRX/C2OUT/P1D/CTED2/INT3_21") (pintype "bidirectional"))
    )
    (net (code "88") (name "unconnected-(U4-RB4{slash}AN9{slash}C2INA{slash}ECCP1{slash}P1A{slash}CTPLS{slash}KBI0-Pad22)") (class "Default")
      (node (ref "U4") (pin "22") (pinfunction "RB4/AN9/C2INA/ECCP1/P1A/CTPLS/KBI0_22") (pintype "bidirectional"))
    )
    (net (code "89") (name "unconnected-(U4-RB5{slash}T0CKI{slash}T3CKI{slash}CCP5{slash}KBI1-Pad23)") (class "Default")
      (node (ref "U4") (pin "23") (pinfunction "RB5/T0CKI/T3CKI/CCP5/KBI1_23") (pintype "bidirectional"))
    )
    (net (code "90") (name "unconnected-(U6-P0_4-Pad24)") (class "Default")
      (node (ref "U6") (pin "24") (pinfunction "P0_4_24") (pintype "bidirectional+no_connect"))
    )
    (net (code "91") (name "unconnected-(U6-P0_6-Pad22)") (class "Default")
      (node (ref "U6") (pin "22") (pinfunction "P0_6_22") (pintype "bidirectional+no_connect"))
    )
    (net (code "92") (name "unconnected-(U6-P0_7-Pad19)") (class "Default")
      (node (ref "U6") (pin "19") (pinfunction "P0_7_19") (pintype "bidirectional+no_connect"))
    )
    (net (code "93") (name "unconnected-(U6-P1_0-Pad18)") (class "Default")
      (node (ref "U6") (pin "18") (pinfunction "P1_0_18") (pintype "bidirectional+no_connect"))
    )
    (net (code "94") (name "unconnected-(U6-P1_1-Pad17)") (class "Default")
      (node (ref "U6") (pin "17") (pinfunction "P1_1_17") (pintype "bidirectional+no_connect"))
    )
    (net (code "95") (name "unconnected-(U6-P1_2-Pad16)") (class "Default")
      (node (ref "U6") (pin "16") (pinfunction "P1_2_16") (pintype "bidirectional+no_connect"))
    )
    (net (code "96") (name "unconnected-(U6-P1_3-Pad15)") (class "Default")
      (node (ref "U6") (pin "15") (pinfunction "P1_3_15") (pintype "bidirectional+no_connect"))
    )
    (net (code "97") (name "unconnected-(U6-P1_4-Pad14)") (class "Default")
      (node (ref "U6") (pin "14") (pinfunction "P1_4_14") (pintype "bidirectional+no_connect"))
    )
    (net (code "98") (name "unconnected-(U6-P1_5-Pad13)") (class "Default")
      (node (ref "U6") (pin "13") (pinfunction "P1_5_13") (pintype "bidirectional+no_connect"))
    )
    (net (code "99") (name "unconnected-(U6-P2_0-Pad6)") (class "Default")
      (node (ref "U6") (pin "6") (pinfunction "P2_0_6") (pintype "bidirectional+no_connect"))
    )
    (net (code "100") (name "unconnected-(U6-VDD_USB-Pad9)") (class "Default")
      (node (ref "U6") (pin "9") (pinfunction "VDD_USB_9") (pintype "power_in+no_connect"))
    )
    (net (code "101") (name "unconnected-(U7-ADC1-Pad16)") (class "Default")
      (node (ref "U7") (pin "16") (pinfunction "ADC1_16") (pintype "input+no_connect"))
    )
    (net (code "102") (name "unconnected-(U7-ADC2-Pad15)") (class "Default")
      (node (ref "U7") (pin "15") (pinfunction "ADC2_15") (pintype "input+no_connect"))
    )
    (net (code "103") (name "unconnected-(U7-ADC3-Pad13)") (class "Default")
      (node (ref "U7") (pin "13") (pinfunction "ADC3_13") (pintype "input+no_connect"))
    )
    (net (code "104") (name "unconnected-(U7-INT1-Pad11)") (class "Default")
      (node (ref "U7") (pin "11") (pinfunction "INT1_11") (pintype "output+no_connect"))
    )
    (net (code "105") (name "unconnected-(U7-INT2-Pad9)") (class "Default")
      (node (ref "U7") (pin "9") (pinfunction "INT2_9") (pintype "output+no_connect"))
    )
    (net (code "106") (name "unconnected-(U7-NC-Pad2)") (class "Default")
      (node (ref "U7") (pin "2") (pinfunction "NC_2") (pintype "passive+no_connect"))
    )
    (net (code "107") (name "unconnected-(U7-NC-Pad3)") (class "Default")
      (node (ref "U7") (pin "3") (pinfunction "NC_3") (pintype "passive+no_connect"))
    )
  )
)
